# aspirin.net
KiCad netlist of a schematic drawn in EAGLE
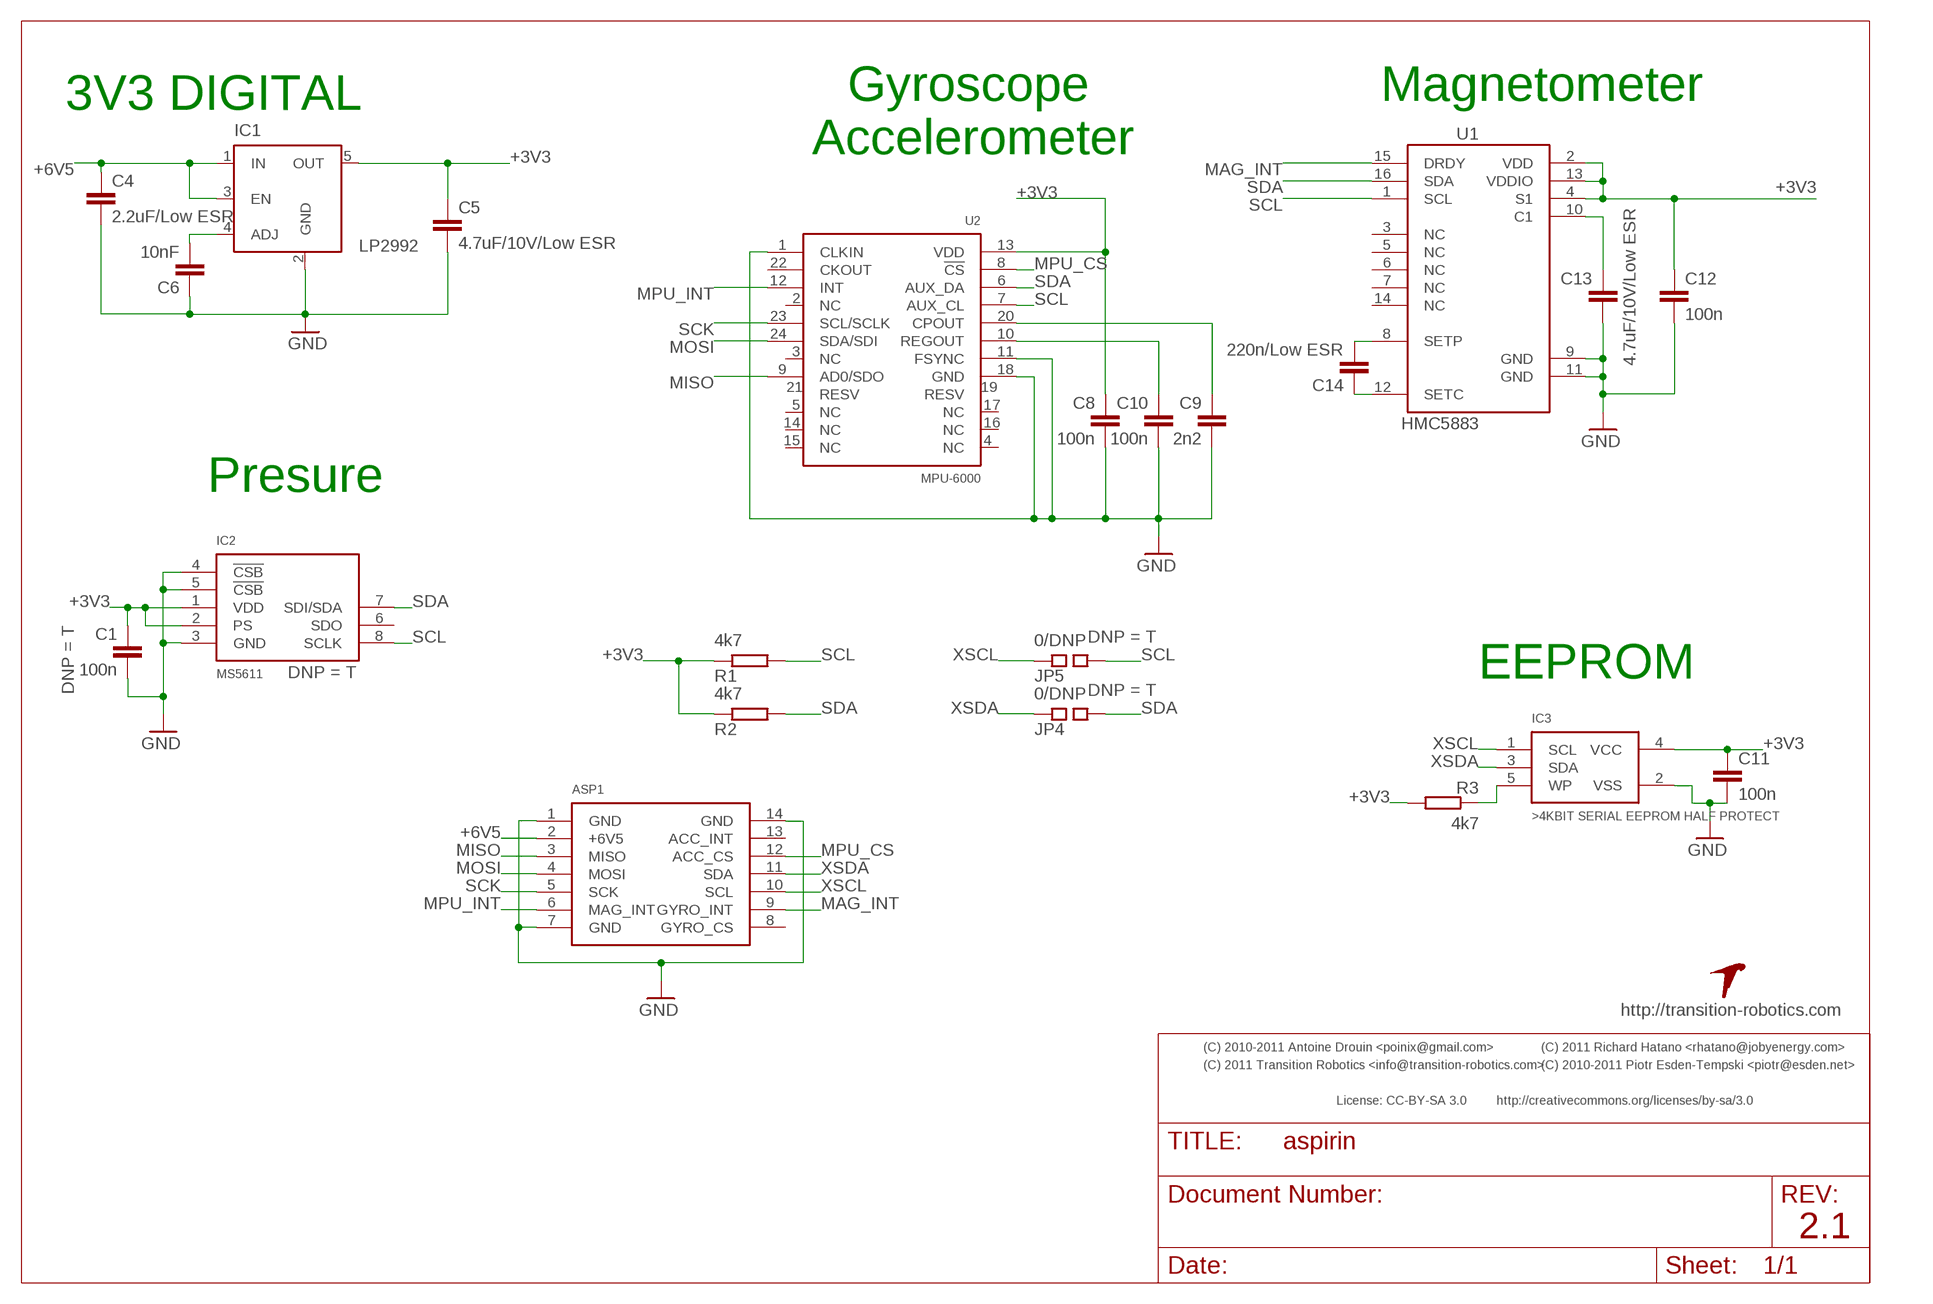
[diagram p0: schematic, sheet 1]

(export (version "E")
  (design (tool "Eeschema 10.0.6"))
  (components
    (comp (ref "ASP1")
      (value "ASPIRIN")
      (footprint "eagle-import:ASPIRIN_CASTELLATED")
      (fields (field (name "PARTNO") "pcb-aspirin"))
      (libsource (lib "eagle-import") (part "ASPIRIN"))
    )
    (comp (ref "C1")
      (value "100n")
      (footprint "eagle-import:0402-CAP")
      (fields (field (name "DNP") "T") (field (name "PARTNO") "cap-cer-0402-100n"))
      (libsource (lib "eagle-import") (part "CAPACITOR-0402"))
    )
    (comp (ref "C4")
      (value "2.2uF/Low ESR")
      (footprint "eagle-import:0603-CAP")
      (fields (field (name "PARTNO") "cap-cer-0603-2u2"))
      (libsource (lib "eagle-import") (part "CAPACITOR-0603"))
    )
    (comp (ref "C5")
      (value "4.7uF/10V/Low ESR")
      (footprint "eagle-import:0603-CAP")
      (fields (field (name "PARTNO") "cap-cer-0603-4u7"))
      (libsource (lib "eagle-import") (part "CAPACITOR-0603"))
    )
    (comp (ref "C6")
      (value "10nF")
      (footprint "eagle-import:0402-CAP")
      (fields (field (name "PARTNO") "cap-cer-0402-10n"))
      (libsource (lib "eagle-import") (part "CAPACITOR-0402"))
    )
    (comp (ref "C8")
      (value "100n")
      (footprint "eagle-import:0402-CAP")
      (fields (field (name "PARTNO") "cap-cer-0402-100n"))
      (libsource (lib "eagle-import") (part "CAPACITOR-0402"))
    )
    (comp (ref "C9")
      (value "2n2")
      (footprint "eagle-import:0402-CAP")
      (fields (field (name "PARTNO") "cap-cer-0402-2n2"))
      (libsource (lib "eagle-import") (part "CAPACITOR-0402"))
    )
    (comp (ref "C10")
      (value "100n")
      (footprint "eagle-import:0402-CAP")
      (fields (field (name "PARTNO") "cap-cer-0402-100n"))
      (libsource (lib "eagle-import") (part "CAPACITOR-0402"))
    )
    (comp (ref "C11")
      (value "100n")
      (footprint "eagle-import:0402-CAP")
      (fields (field (name "PARTNO") "cap-cer-0402-100n"))
      (libsource (lib "eagle-import") (part "CAPACITOR-0402"))
    )
    (comp (ref "C12")
      (value "100n")
      (footprint "eagle-import:0402-CAP")
      (fields (field (name "PARTNO") "cap-cer-0402-100n"))
      (libsource (lib "eagle-import") (part "CAPACITOR-0402"))
    )
    (comp (ref "C13")
      (value "4.7uF/10V/Low ESR")
      (footprint "eagle-import:0603-CAP")
      (fields (field (name "PARTNO") "cap-cer-0603-4u7"))
      (libsource (lib "eagle-import") (part "CAPACITOR-0603"))
    )
    (comp (ref "C14")
      (value "220n/Low ESR")
      (footprint "eagle-import:0603-CAP")
      (fields (field (name "PARTNO") "cap-cer-0603-220n"))
      (libsource (lib "eagle-import") (part "CAPACITOR-0603"))
    )
    (comp (ref "IC1")
      (value "LP2992")
      (footprint "eagle-import:SOT23-5")
      (fields (field (name "PARTNO") "vreg-sot-23-5-3v3"))
      (libsource (lib "eagle-import") (part "MIC5219BM5"))
    )
    (comp (ref "IC2")
      (value "MS5611")
      (footprint "eagle-import:QFN-MS5611")
      (fields (field (name "DNP") "T") (field (name "PARTNO") "sensr-qfn-8-baro"))
      (libsource (lib "eagle-import") (part "MS5611"))
    )
    (comp (ref "IC3")
      (value ">4KBIT SERIAL EEPROM HALF PROTECT")
      (footprint "eagle-import:SOT23-5")
      (fields (field (name "PARTNO") "ic-sot-23-5-4k-eeprom"))
      (libsource (lib "eagle-import") (part "I2C_EEPROM-SOT23-5"))
    )
    (comp (ref "JP4")
      (value "0/DNP")
      (footprint "eagle-import:0402-SQJMP")
      (fields (field (name "DNP") "T") (field (name "PARTNO") "res-0402-0"))
      (libsource (lib "eagle-import") (part "SQ_JMP-0402"))
    )
    (comp (ref "JP5")
      (value "0/DNP")
      (footprint "eagle-import:0402-SQJMP")
      (fields (field (name "DNP") "T") (field (name "PARTNO") "res-0402-0"))
      (libsource (lib "eagle-import") (part "SQ_JMP-0402"))
    )
    (comp (ref "R1")
      (value "4k7")
      (footprint "eagle-import:0402-RES")
      (fields (field (name "PARTNO") "res-0402-4k7"))
      (libsource (lib "eagle-import") (part "RESISTOR-0402"))
    )
    (comp (ref "R2")
      (value "4k7")
      (footprint "eagle-import:0402-RES")
      (fields (field (name "PARTNO") "res-0402-4k7"))
      (libsource (lib "eagle-import") (part "RESISTOR-0402"))
    )
    (comp (ref "R3")
      (value "4k7")
      (footprint "eagle-import:0402-RES")
      (fields (field (name "PARTNO") "res-0402-4k7"))
      (libsource (lib "eagle-import") (part "RESISTOR-0402"))
    )
    (comp (ref "U$1")
      (value "TR-LOGO")
      (footprint "eagle-import:TR-LOGO")
      (libsource (lib "eagle-import") (part "TR-LOGO"))
    )
    (comp (ref "U1")
      (value "HMC5883")
      (footprint "eagle-import:PLCC16-HMC5883")
      (fields (field (name "PARTNO") "sensr-plcc-16-mag"))
      (libsource (lib "eagle-import") (part "HMC5883"))
    )
    (comp (ref "U2")
      (value "MPU-6000")
      (footprint "eagle-import:QFN24-NO-PAD")
      (fields (field (name "PARTNO") "sensr-qfn-24-acc-gyro"))
      (libsource (lib "eagle-import") (part "MPU-6000"))
    )
  )
  (nets
    (net (code "1") (name "/+3V3") (class "Default")
      (node (ref "C1") (pin "P$1") (pinfunction "1_P$1") (pintype "passive"))
      (node (ref "C11") (pin "P$1") (pinfunction "1_P$1") (pintype "passive"))
      (node (ref "C12") (pin "P$1") (pinfunction "1_P$1") (pintype "passive"))
      (node (ref "C5") (pin "P$1") (pinfunction "1_P$1") (pintype "passive"))
      (node (ref "C8") (pin "P$1") (pinfunction "1_P$1") (pintype "passive"))
      (node (ref "IC1") (pin "5") (pinfunction "OUT_5") (pintype "output"))
      (node (ref "IC2") (pin "1") (pinfunction "VDD_1") (pintype "bidirectional"))
      (node (ref "IC2") (pin "2") (pinfunction "PS_2") (pintype "bidirectional"))
      (node (ref "IC3") (pin "4") (pinfunction "VCC_4") (pintype "bidirectional"))
      (node (ref "R1") (pin "P$1") (pinfunction "1_P$1") (pintype "passive"))
      (node (ref "R2") (pin "P$1") (pinfunction "1_P$1") (pintype "passive"))
      (node (ref "R3") (pin "P$2") (pinfunction "2_P$2") (pintype "passive"))
      (node (ref "U1") (pin "13") (pinfunction "VDDIO_13") (pintype "power_in"))
      (node (ref "U1") (pin "2") (pinfunction "VDD_2") (pintype "power_in"))
      (node (ref "U1") (pin "4") (pinfunction "S1_4") (pintype "power_in"))
      (node (ref "U2") (pin "13") (pinfunction "VDD_13") (pintype "bidirectional"))
    )
    (net (code "2") (name "/+6V5") (class "Default")
      (node (ref "ASP1") (pin "2") (pinfunction "+6V5_2") (pintype "bidirectional"))
      (node (ref "C4") (pin "P$1") (pinfunction "1_P$1") (pintype "passive"))
      (node (ref "IC1") (pin "1") (pinfunction "IN_1") (pintype "input"))
      (node (ref "IC1") (pin "3") (pinfunction "EN_3") (pintype "input"))
    )
    (net (code "3") (name "/MAG_INT") (class "Default")
      (node (ref "ASP1") (pin "9") (pinfunction "GYRO_INT_9") (pintype "bidirectional"))
      (node (ref "U1") (pin "15") (pinfunction "DRDY_15") (pintype "bidirectional"))
    )
    (net (code "4") (name "/MISO") (class "Default")
      (node (ref "ASP1") (pin "3") (pinfunction "MISO_3") (pintype "bidirectional"))
      (node (ref "U2") (pin "9") (pinfunction "AD0/SDO_9") (pintype "bidirectional"))
    )
    (net (code "5") (name "/MOSI") (class "Default")
      (node (ref "ASP1") (pin "4") (pinfunction "MOSI_4") (pintype "bidirectional"))
      (node (ref "U2") (pin "24") (pinfunction "SDA/SDI_24") (pintype "bidirectional"))
    )
    (net (code "6") (name "/MPU_CS") (class "Default")
      (node (ref "ASP1") (pin "12") (pinfunction "ACC_CS_12") (pintype "bidirectional"))
      (node (ref "U2") (pin "8") (pinfunction "~{CS}_8") (pintype "bidirectional"))
    )
    (net (code "7") (name "/MPU_INT") (class "Default")
      (node (ref "ASP1") (pin "6") (pinfunction "MAG_INT_6") (pintype "bidirectional"))
      (node (ref "U2") (pin "12") (pinfunction "INT_12") (pintype "bidirectional"))
    )
    (net (code "8") (name "/SCK") (class "Default")
      (node (ref "ASP1") (pin "5") (pinfunction "SCK_5") (pintype "bidirectional"))
      (node (ref "U2") (pin "23") (pinfunction "SCL/SCLK_23") (pintype "bidirectional"))
    )
    (net (code "9") (name "/SCL") (class "Default")
      (node (ref "IC2") (pin "8") (pinfunction "SCLK_8") (pintype "bidirectional"))
      (node (ref "JP5") (pin "P$2") (pinfunction "2_P$2") (pintype "passive"))
      (node (ref "R1") (pin "P$2") (pinfunction "2_P$2") (pintype "passive"))
      (node (ref "U1") (pin "1") (pinfunction "SCL_1") (pintype "bidirectional"))
      (node (ref "U2") (pin "7") (pinfunction "AUX_CL_7") (pintype "bidirectional"))
    )
    (net (code "10") (name "/SDA") (class "Default")
      (node (ref "IC2") (pin "7") (pinfunction "SDI/SDA_7") (pintype "bidirectional"))
      (node (ref "JP4") (pin "P$2") (pinfunction "2_P$2") (pintype "passive"))
      (node (ref "R2") (pin "P$2") (pinfunction "2_P$2") (pintype "passive"))
      (node (ref "U1") (pin "16") (pinfunction "SDA_16") (pintype "bidirectional"))
      (node (ref "U2") (pin "6") (pinfunction "AUX_DA_6") (pintype "bidirectional"))
    )
    (net (code "11") (name "/XSCL") (class "Default")
      (node (ref "ASP1") (pin "10") (pinfunction "SCL_10") (pintype "bidirectional"))
      (node (ref "IC3") (pin "1") (pinfunction "SCL_1") (pintype "bidirectional"))
      (node (ref "JP5") (pin "P$1") (pinfunction "1_P$1") (pintype "passive"))
    )
    (net (code "12") (name "/XSDA") (class "Default")
      (node (ref "ASP1") (pin "11") (pinfunction "SDA_11") (pintype "bidirectional"))
      (node (ref "IC3") (pin "3") (pinfunction "SDA_3") (pintype "bidirectional"))
      (node (ref "JP4") (pin "P$1") (pinfunction "1_P$1") (pintype "passive"))
    )
    (net (code "13") (name "GND") (class "Default")
      (node (ref "ASP1") (pin "1") (pinfunction "GND_1") (pintype "bidirectional"))
      (node (ref "ASP1") (pin "14") (pinfunction "GND_14") (pintype "bidirectional"))
      (node (ref "ASP1") (pin "7") (pinfunction "GND_7") (pintype "bidirectional"))
      (node (ref "C1") (pin "P$2") (pinfunction "2_P$2") (pintype "passive"))
      (node (ref "C10") (pin "P$2") (pinfunction "2_P$2") (pintype "passive"))
      (node (ref "C11") (pin "P$2") (pinfunction "2_P$2") (pintype "passive"))
      (node (ref "C12") (pin "P$2") (pinfunction "2_P$2") (pintype "passive"))
      (node (ref "C13") (pin "P$2") (pinfunction "2_P$2") (pintype "passive"))
      (node (ref "C4") (pin "P$2") (pinfunction "2_P$2") (pintype "passive"))
      (node (ref "C5") (pin "P$2") (pinfunction "2_P$2") (pintype "passive"))
      (node (ref "C6") (pin "P$1") (pinfunction "1_P$1") (pintype "passive"))
      (node (ref "C8") (pin "P$2") (pinfunction "2_P$2") (pintype "passive"))
      (node (ref "C9") (pin "P$2") (pinfunction "2_P$2") (pintype "passive"))
      (node (ref "IC1") (pin "2") (pinfunction "GND_2") (pintype "power_in"))
      (node (ref "IC2") (pin "3") (pinfunction "GND_3") (pintype "bidirectional"))
      (node (ref "IC2") (pin "4") (pinfunction "~{CSB}_4") (pintype "bidirectional"))
      (node (ref "IC2") (pin "5") (pinfunction "~{CSB}_5") (pintype "bidirectional"))
      (node (ref "IC3") (pin "2") (pinfunction "VSS_2") (pintype "bidirectional"))
      (node (ref "U1") (pin "11") (pinfunction "GND_11") (pintype "power_in"))
      (node (ref "U1") (pin "9") (pinfunction "GND_9") (pintype "power_in"))
      (node (ref "U2") (pin "1") (pinfunction "CLKIN_1") (pintype "bidirectional"))
      (node (ref "U2") (pin "11") (pinfunction "FSYNC_11") (pintype "bidirectional"))
      (node (ref "U2") (pin "18") (pinfunction "GND_18") (pintype "bidirectional"))
    )
    (net (code "14") (name "Net-(C6-2)") (class "Default")
      (node (ref "C6") (pin "P$2") (pinfunction "2_P$2") (pintype "passive"))
      (node (ref "IC1") (pin "4") (pinfunction "ADJ_4") (pintype "passive"))
    )
    (net (code "15") (name "Net-(C9-1)") (class "Default")
      (node (ref "C9") (pin "P$1") (pinfunction "1_P$1") (pintype "passive"))
      (node (ref "U2") (pin "20") (pinfunction "CPOUT_20") (pintype "bidirectional"))
    )
    (net (code "16") (name "Net-(C10-1)") (class "Default")
      (node (ref "C10") (pin "P$1") (pinfunction "1_P$1") (pintype "passive"))
      (node (ref "U2") (pin "10") (pinfunction "REGOUT_10") (pintype "bidirectional"))
    )
    (net (code "17") (name "Net-(C13-1)") (class "Default")
      (node (ref "C13") (pin "P$1") (pinfunction "1_P$1") (pintype "passive"))
      (node (ref "U1") (pin "10") (pinfunction "C1_10") (pintype "bidirectional"))
    )
    (net (code "18") (name "Net-(C14-1)") (class "Default")
      (node (ref "C14") (pin "P$1") (pinfunction "1_P$1") (pintype "passive"))
      (node (ref "U1") (pin "12") (pinfunction "SETC_12") (pintype "bidirectional"))
    )
    (net (code "19") (name "Net-(C14-2)") (class "Default")
      (node (ref "C14") (pin "P$2") (pinfunction "2_P$2") (pintype "passive"))
      (node (ref "U1") (pin "8") (pinfunction "SETP_8") (pintype "bidirectional"))
    )
    (net (code "20") (name "Net-(IC3-WP)") (class "Default")
      (node (ref "IC3") (pin "5") (pinfunction "WP_5") (pintype "bidirectional"))
      (node (ref "R3") (pin "P$1") (pinfunction "1_P$1") (pintype "passive"))
    )
    (net (code "21") (name "unconnected-(ASP1-ACC_INT-Pad13)") (class "Default")
      (node (ref "ASP1") (pin "13") (pinfunction "ACC_INT_13") (pintype "bidirectional"))
    )
    (net (code "22") (name "unconnected-(ASP1-GYRO_CS-Pad8)") (class "Default")
      (node (ref "ASP1") (pin "8") (pinfunction "GYRO_CS_8") (pintype "bidirectional"))
    )
    (net (code "23") (name "unconnected-(IC2-SDO-Pad6)") (class "Default")
      (node (ref "IC2") (pin "6") (pinfunction "SDO_6") (pintype "bidirectional"))
    )
    (net (code "24") (name "unconnected-(U1-NC-Pad3)") (class "Default")
      (node (ref "U1") (pin "3") (pinfunction "NC_3") (pintype "no_connect"))
    )
    (net (code "25") (name "unconnected-(U1-NC-Pad5)") (class "Default")
      (node (ref "U1") (pin "5") (pinfunction "NC_5") (pintype "no_connect"))
    )
    (net (code "26") (name "unconnected-(U1-NC-Pad6)") (class "Default")
      (node (ref "U1") (pin "6") (pinfunction "NC_6") (pintype "no_connect"))
    )
    (net (code "27") (name "unconnected-(U1-NC-Pad7)") (class "Default")
      (node (ref "U1") (pin "7") (pinfunction "NC_7") (pintype "no_connect"))
    )
    (net (code "28") (name "unconnected-(U1-NC-Pad14)") (class "Default")
      (node (ref "U1") (pin "14") (pinfunction "NC_14") (pintype "no_connect"))
    )
    (net (code "29") (name "unconnected-(U2-CKOUT-Pad22)") (class "Default")
      (node (ref "U2") (pin "22") (pinfunction "CKOUT_22") (pintype "bidirectional"))
    )
    (net (code "30") (name "unconnected-(U2-NC-Pad2)") (class "Default")
      (node (ref "U2") (pin "2") (pinfunction "NC_2") (pintype "bidirectional"))
    )
    (net (code "31") (name "unconnected-(U2-NC-Pad3)") (class "Default")
      (node (ref "U2") (pin "3") (pinfunction "NC_3") (pintype "bidirectional"))
    )
    (net (code "32") (name "unconnected-(U2-NC-Pad4)") (class "Default")
      (node (ref "U2") (pin "4") (pinfunction "NC_4") (pintype "bidirectional"))
    )
    (net (code "33") (name "unconnected-(U2-NC-Pad5)") (class "Default")
      (node (ref "U2") (pin "5") (pinfunction "NC_5") (pintype "bidirectional"))
    )
    (net (code "34") (name "unconnected-(U2-NC-Pad14)") (class "Default")
      (node (ref "U2") (pin "14") (pinfunction "NC_14") (pintype "bidirectional"))
    )
    (net (code "35") (name "unconnected-(U2-NC-Pad15)") (class "Default")
      (node (ref "U2") (pin "15") (pinfunction "NC_15") (pintype "bidirectional"))
    )
    (net (code "36") (name "unconnected-(U2-NC-Pad16)") (class "Default")
      (node (ref "U2") (pin "16") (pinfunction "NC_16") (pintype "bidirectional"))
    )
    (net (code "37") (name "unconnected-(U2-NC-Pad17)") (class "Default")
      (node (ref "U2") (pin "17") (pinfunction "NC_17") (pintype "bidirectional"))
    )
    (net (code "38") (name "unconnected-(U2-RESV-Pad19)") (class "Default")
      (node (ref "U2") (pin "19") (pinfunction "RESV_19") (pintype "bidirectional"))
    )
    (net (code "39") (name "unconnected-(U2-RESV-Pad21)") (class "Default")
      (node (ref "U2") (pin "21") (pinfunction "RESV_21") (pintype "bidirectional"))
    )
  )
)
